# OZ440-SE130-CAR001-SCH2.net
KiCad netlist of a schematic drawn in Altium Designer
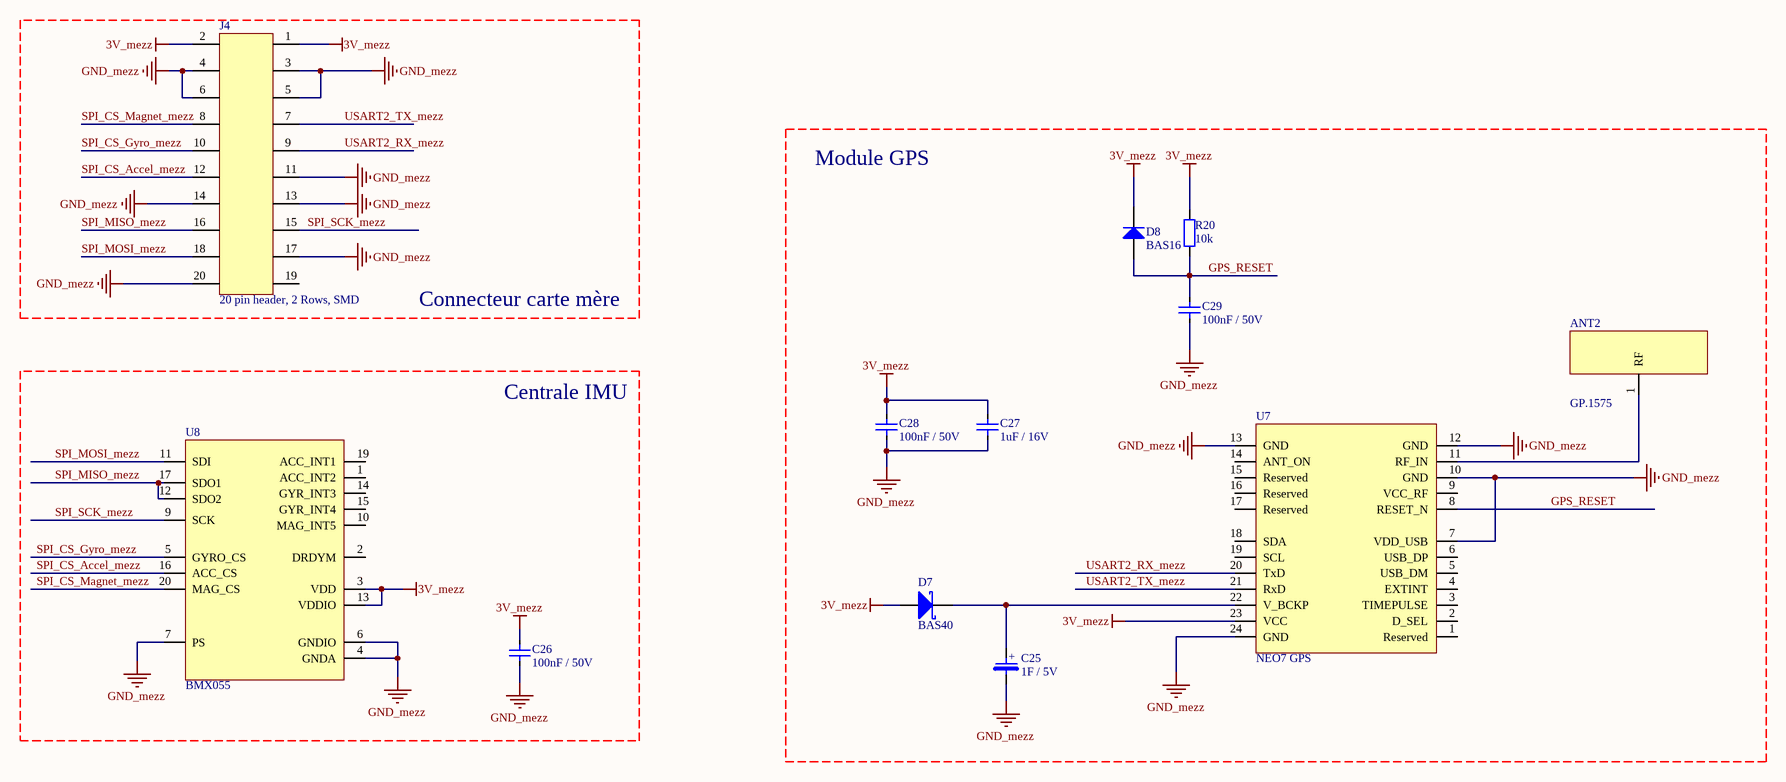
[diagram p0: OZ440-SE130-CAR001-SCH2.SchDoc]

(export (version "E")
  (design (tool "Eeschema 10.0.6"))
  (components
    (comp (ref "ANT2")
      (value "ANT-STD-GPS")
      (footprint "ANT_SMD-SPE-GP_1575")
      (description "35mm GPS patch antenna")
      (fields (field (name "DISPLAYED REFERENCE") "GP.1575") (field (name "MANUFACTURER") "Taoglass"))
      (libsource (lib "lib_NAIO") (part "ANT-STD-GPS"))
    )
    (comp (ref "C25")
      (value "CAP-POL-SMD")
      (footprint "RADIAL-STD-P20-H5-D20")
      (description "1F 5V capacitor")
      (fields
        (field (name "DISPLAYED REFERENCE") "1F / 5V")
        (field (name "MANUFACTURER") "Cornell Dubillier")
      )
      (libsource (lib "lib_NAIO") (part "CAP-POL-SMD"))
    )
    (comp (ref "C26")
      (value "CAP-SMD")
      (footprint "C0805-STD")
      (description "0805 100nF / 50V  X7R ceramic capacitor")
      (fields
        (field (name "DISPLAYED REFERENCE") "100nF / 50V")
        (field (name "TOLERANCE") "+/- 10%")
        (field (name "MANUFACTURER") "vishay")
      )
      (libsource (lib "lib_NAIO") (part "CAP-SMD"))
    )
    (comp (ref "C27")
      (value "CAP-SMD")
      (footprint "C0805-STD")
      (description "0805 1uF / 16V X7R ceramic capacitor")
      (fields
        (field (name "DISPLAYED REFERENCE") "1uF / 16V")
        (field (name "TOLERANCE") "+/- 10%")
        (field (name "MANUFACTURER") "Kemet")
      )
      (libsource (lib "lib_NAIO") (part "CAP-SMD"))
    )
    (comp (ref "C28")
      (value "CAP-SMD")
      (footprint "C0805-STD")
      (description "0805 100nF / 50V  X7R ceramic capacitor")
      (fields
        (field (name "DISPLAYED REFERENCE") "100nF / 50V")
        (field (name "TOLERANCE") "+/- 10%")
        (field (name "MANUFACTURER") "vishay")
      )
      (libsource (lib "lib_NAIO") (part "CAP-SMD"))
    )
    (comp (ref "C29")
      (value "CAP-SMD")
      (footprint "C0805-STD")
      (description "0805 100nF / 50V  X7R ceramic capacitor")
      (fields
        (field (name "DISPLAYED REFERENCE") "100nF / 50V")
        (field (name "TOLERANCE") "+/- 10%")
        (field (name "MANUFACTURER") "vishay")
      )
      (libsource (lib "lib_NAIO") (part "CAP-SMD"))
    )
    (comp (ref "D7")
      (value "BAS40-SOT23")
      (footprint "SOT23-STD")
      (description "40V / 120mA signal schottky diode")
      (fields (field (name "DISPLAYED REFERENCE") "BAS40") (field (name "MANUFACTURER") "NXP"))
      (libsource (lib "lib_NAIO") (part "BAS40-SOT23"))
    )
    (comp (ref "D8")
      (value "BAS16-SOT23")
      (footprint "SOT23-STD")
      (description "100V / 120mA signal  diode")
      (fields (field (name "DISPLAYED REFERENCE") "BAS16") (field (name "MANUFACTURER") "NXP"))
      (libsource (lib "lib_NAIO") (part "BAS16-SOT23"))
    )
    (comp (ref "J4")
      (value "CONN-STD-20P_2ROW")
      (footprint "CONN-SPE_TSM110-02-T")
      (description "20 pin header, 2.54mm, SMD")
      (fields
        (field (name "DISPLAYED REFERENCE") "20 pin header, 2 Rows, SMD")
        (field (name "MANUFACTURER") "SAMTEC")
      )
      (libsource (lib "lib_NAIO") (part "CONN-STD-20P_2ROW"))
    )
    (comp (ref "R20")
      (value "RES-SMD")
      (footprint "R0805-STD")
      (description "10k Ohm 0805 SMD resistor")
      (fields
        (field (name "DISPLAYED REFERENCE") "10k")
        (field (name "TOLERANCE") "1 %")
        (field (name "MANUFACTURER") "Vishay")
      )
      (libsource (lib "lib_NAIO") (part "RES-SMD"))
    )
    (comp (ref "U7")
      (value "NEO_7-SMD24")
      (footprint "SMD24-SPE-NEO7")
      (description "Neo 7 GPS module")
      (fields (field (name "DISPLAYED REFERENCE") "NEO7 GPS") (field (name "MANUFACTURER") "Ublox"))
      (libsource (lib "lib_NAIO") (part "NEO_7-SMD24"))
    )
    (comp (ref "U8")
      (value "BMX055-LGA20")
      (footprint "LGA20-SPE-BMX055")
      (description "9 axis SPI IMU sensor")
      (fields (field (name "DISPLAYED REFERENCE") "BMX055") (field (name "MANUFACTURER") "Bosch"))
      (libsource (lib "lib_NAIO") (part "BMX055-LGA20"))
    )
  )
  (nets
    (net (code "1") (name "/GPS_RESET") (class "Default")
      (node (ref "C29") (pin "2") (pinfunction "2_2") (pintype "passive"))
      (node (ref "D8") (pin "1") (pinfunction "A_1") (pintype "passive"))
      (node (ref "R20") (pin "1") (pinfunction "1_1") (pintype "passive"))
      (node (ref "U7") (pin "8") (pinfunction "RESET_N_8") (pintype "passive"))
    )
    (net (code "2") (name "/SPI_CS_Accel_mezz") (class "Default")
      (node (ref "J4") (pin "12") (pinfunction "12_12") (pintype "passive"))
      (node (ref "U8") (pin "16") (pinfunction "ACC_CS_16") (pintype "passive"))
    )
    (net (code "3") (name "/SPI_CS_Gyro_mezz") (class "Default")
      (node (ref "J4") (pin "10") (pinfunction "10_10") (pintype "passive"))
      (node (ref "U8") (pin "5") (pinfunction "GYRO_CS_5") (pintype "passive"))
    )
    (net (code "4") (name "/SPI_CS_Magnet_mezz") (class "Default")
      (node (ref "J4") (pin "8") (pinfunction "8_8") (pintype "passive"))
      (node (ref "U8") (pin "20") (pinfunction "MAG_CS_20") (pintype "passive"))
    )
    (net (code "5") (name "/SPI_MISO_mezz") (class "Default")
      (node (ref "J4") (pin "16") (pinfunction "16_16") (pintype "passive"))
      (node (ref "U8") (pin "12") (pinfunction "SDO2_12") (pintype "passive"))
      (node (ref "U8") (pin "17") (pinfunction "SDO1_17") (pintype "passive"))
    )
    (net (code "6") (name "/SPI_MOSI_mezz") (class "Default")
      (node (ref "J4") (pin "18") (pinfunction "18_18") (pintype "passive"))
      (node (ref "U8") (pin "11") (pinfunction "SDI_11") (pintype "passive"))
    )
    (net (code "7") (name "/SPI_SCK_mezz") (class "Default")
      (node (ref "J4") (pin "15") (pinfunction "15_15") (pintype "passive"))
      (node (ref "U8") (pin "9") (pinfunction "SCK_9") (pintype "passive"))
    )
    (net (code "8") (name "/USART2_RX_mezz") (class "Default")
      (node (ref "J4") (pin "9") (pinfunction "9_9") (pintype "passive"))
      (node (ref "U7") (pin "20") (pinfunction "TxD_20") (pintype "passive"))
    )
    (net (code "9") (name "/USART2_TX_mezz") (class "Default")
      (node (ref "J4") (pin "7") (pinfunction "7_7") (pintype "passive"))
      (node (ref "U7") (pin "21") (pinfunction "RxD_21") (pintype "passive"))
    )
    (net (code "10") (name "3V_mezz") (class "Default")
      (node (ref "C26") (pin "2") (pinfunction "2_2") (pintype "passive"))
      (node (ref "C27") (pin "2") (pinfunction "2_2") (pintype "passive"))
      (node (ref "C28") (pin "2") (pinfunction "2_2") (pintype "passive"))
      (node (ref "D7") (pin "1") (pinfunction "A_1") (pintype "passive"))
      (node (ref "D8") (pin "3") (pinfunction "K_3") (pintype "passive"))
      (node (ref "J4") (pin "1") (pinfunction "1_1") (pintype "passive"))
      (node (ref "J4") (pin "2") (pinfunction "2_2") (pintype "passive"))
      (node (ref "R20") (pin "2") (pinfunction "2_2") (pintype "passive"))
      (node (ref "U7") (pin "23") (pinfunction "VCC_23") (pintype "passive"))
      (node (ref "U8") (pin "13") (pinfunction "VDDIO_13") (pintype "passive"))
      (node (ref "U8") (pin "3") (pinfunction "VDD_3") (pintype "passive"))
    )
    (net (code "11") (name "GND_mezz") (class "Default")
      (node (ref "C25") (pin "2") (pinfunction "2_2") (pintype "passive"))
      (node (ref "C26") (pin "1") (pinfunction "1_1") (pintype "passive"))
      (node (ref "C27") (pin "1") (pinfunction "1_1") (pintype "passive"))
      (node (ref "C28") (pin "1") (pinfunction "1_1") (pintype "passive"))
      (node (ref "C29") (pin "1") (pinfunction "1_1") (pintype "passive"))
      (node (ref "J4") (pin "11") (pinfunction "11_11") (pintype "passive"))
      (node (ref "J4") (pin "13") (pinfunction "13_13") (pintype "passive"))
      (node (ref "J4") (pin "14") (pinfunction "14_14") (pintype "passive"))
      (node (ref "J4") (pin "17") (pinfunction "17_17") (pintype "passive"))
      (node (ref "J4") (pin "20") (pinfunction "20_20") (pintype "passive"))
      (node (ref "J4") (pin "3") (pinfunction "3_3") (pintype "passive"))
      (node (ref "J4") (pin "4") (pinfunction "4_4") (pintype "passive"))
      (node (ref "J4") (pin "5") (pinfunction "5_5") (pintype "passive"))
      (node (ref "J4") (pin "6") (pinfunction "6_6") (pintype "passive"))
      (node (ref "U7") (pin "10") (pinfunction "GND_10") (pintype "passive"))
      (node (ref "U7") (pin "12") (pinfunction "GND_12") (pintype "passive"))
      (node (ref "U7") (pin "13") (pinfunction "GND_13") (pintype "passive"))
      (node (ref "U7") (pin "24") (pinfunction "GND_24") (pintype "passive"))
      (node (ref "U7") (pin "7") (pinfunction "VDD_USB_7") (pintype "passive"))
      (node (ref "U8") (pin "4") (pinfunction "GNDA_4") (pintype "passive"))
      (node (ref "U8") (pin "6") (pinfunction "GNDIO_6") (pintype "passive"))
      (node (ref "U8") (pin "7") (pinfunction "PS_7") (pintype "passive"))
    )
    (net (code "12") (name "Net-(ANT2-RF)") (class "Default")
      (node (ref "ANT2") (pin "1") (pinfunction "RF_1") (pintype "passive"))
      (node (ref "U7") (pin "11") (pinfunction "RF_IN_11") (pintype "passive"))
    )
    (net (code "13") (name "Net-(D7-K)") (class "Default")
      (node (ref "C25") (pin "1") (pinfunction "1_1") (pintype "passive"))
      (node (ref "D7") (pin "3") (pinfunction "K_3") (pintype "passive"))
      (node (ref "U7") (pin "22") (pinfunction "V_BCKP_22") (pintype "passive"))
    )
    (net (code "14") (name "unconnected-(J4-Pad19)") (class "Default")
      (node (ref "J4") (pin "19") (pinfunction "19_19") (pintype "passive"))
    )
    (net (code "15") (name "unconnected-(U7-ANT_ON-Pad14)") (class "Default")
      (node (ref "U7") (pin "14") (pinfunction "ANT_ON_14") (pintype "passive"))
    )
    (net (code "16") (name "unconnected-(U7-D_SEL-Pad2)") (class "Default")
      (node (ref "U7") (pin "2") (pinfunction "D_SEL_2") (pintype "passive"))
    )
    (net (code "17") (name "unconnected-(U7-EXTINT-Pad4)") (class "Default")
      (node (ref "U7") (pin "4") (pinfunction "EXTINT_4") (pintype "passive"))
    )
    (net (code "18") (name "unconnected-(U7-Reserved-Pad1)") (class "Default")
      (node (ref "U7") (pin "1") (pinfunction "Reserved_1") (pintype "passive"))
    )
    (net (code "19") (name "unconnected-(U7-Reserved-Pad15)") (class "Default")
      (node (ref "U7") (pin "15") (pinfunction "Reserved_15") (pintype "passive"))
    )
    (net (code "20") (name "unconnected-(U7-Reserved-Pad16)") (class "Default")
      (node (ref "U7") (pin "16") (pinfunction "Reserved_16") (pintype "passive"))
    )
    (net (code "21") (name "unconnected-(U7-Reserved-Pad17)") (class "Default")
      (node (ref "U7") (pin "17") (pinfunction "Reserved_17") (pintype "passive"))
    )
    (net (code "22") (name "unconnected-(U7-SCL-Pad19)") (class "Default")
      (node (ref "U7") (pin "19") (pinfunction "SCL_19") (pintype "passive"))
    )
    (net (code "23") (name "unconnected-(U7-SDA-Pad18)") (class "Default")
      (node (ref "U7") (pin "18") (pinfunction "SDA_18") (pintype "passive"))
    )
    (net (code "24") (name "unconnected-(U7-TIMEPULSE-Pad3)") (class "Default")
      (node (ref "U7") (pin "3") (pinfunction "TIMEPULSE_3") (pintype "passive"))
    )
    (net (code "25") (name "unconnected-(U7-USB_DM-Pad5)") (class "Default")
      (node (ref "U7") (pin "5") (pinfunction "USB_DM_5") (pintype "passive"))
    )
    (net (code "26") (name "unconnected-(U7-USB_DP-Pad6)") (class "Default")
      (node (ref "U7") (pin "6") (pinfunction "USB_DP_6") (pintype "passive"))
    )
    (net (code "27") (name "unconnected-(U7-VCC_RF-Pad9)") (class "Default")
      (node (ref "U7") (pin "9") (pinfunction "VCC_RF_9") (pintype "passive"))
    )
    (net (code "28") (name "unconnected-(U8-ACC_INT1-Pad19)") (class "Default")
      (node (ref "U8") (pin "19") (pinfunction "ACC_INT1_19") (pintype "passive"))
    )
    (net (code "29") (name "unconnected-(U8-ACC_INT2-Pad1)") (class "Default")
      (node (ref "U8") (pin "1") (pinfunction "ACC_INT2_1") (pintype "passive"))
    )
    (net (code "30") (name "unconnected-(U8-DRDYM-Pad2)") (class "Default")
      (node (ref "U8") (pin "2") (pinfunction "DRDYM_2") (pintype "passive"))
    )
    (net (code "31") (name "unconnected-(U8-GYR_INT3-Pad14)") (class "Default")
      (node (ref "U8") (pin "14") (pinfunction "GYR_INT3_14") (pintype "passive"))
    )
    (net (code "32") (name "unconnected-(U8-GYR_INT4-Pad15)") (class "Default")
      (node (ref "U8") (pin "15") (pinfunction "GYR_INT4_15") (pintype "passive"))
    )
    (net (code "33") (name "unconnected-(U8-MAG_INT5-Pad10)") (class "Default")
      (node (ref "U8") (pin "10") (pinfunction "MAG_INT5_10") (pintype "passive"))
    )
  )
)
